# basePCB.net
KiCad netlist of a schematic drawn in EAGLE
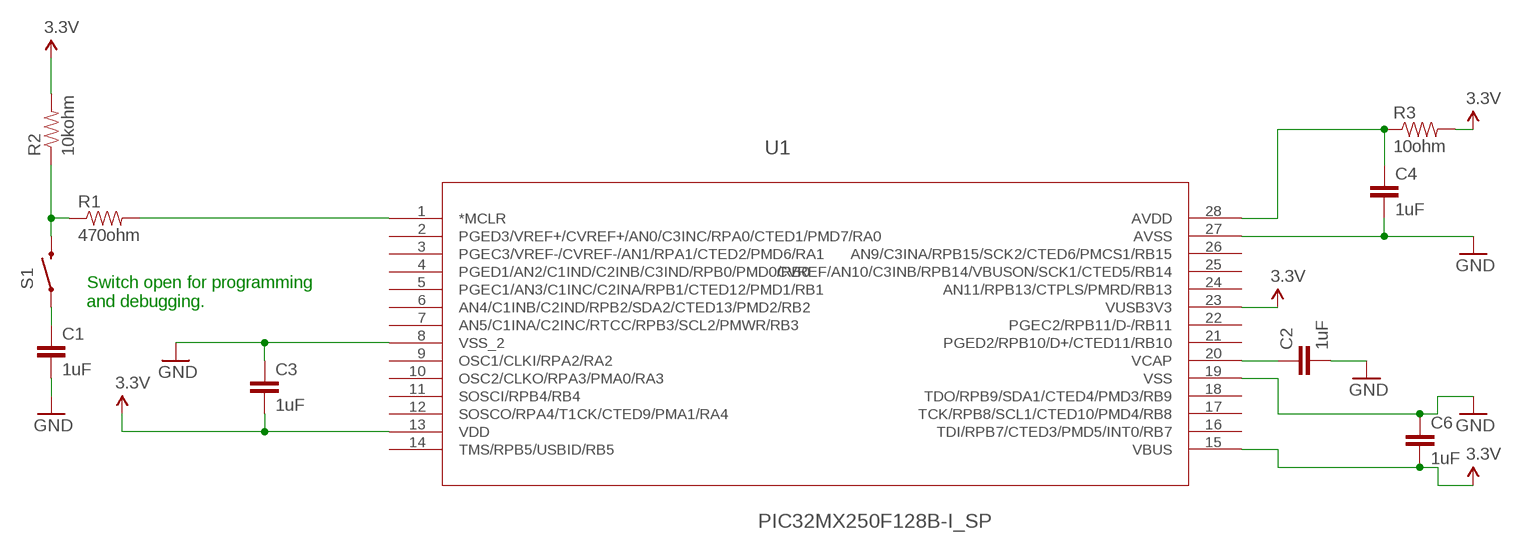
[diagram p0: schematic, sheet 1]

(export (version "E")
  (design (tool "Eeschema 10.0.6"))
  (components
    (comp (ref "C1")
      (value "1uF")
      (footprint "eagle-import:CAP-PTH-SMALL")
      (libsource (lib "eagle-import") (part "CAPPTH"))
    )
    (comp (ref "C2")
      (value "1uF")
      (footprint "eagle-import:CAP-PTH-SMALL")
      (libsource (lib "eagle-import") (part "CAPPTH"))
    )
    (comp (ref "C3")
      (value "1uF")
      (footprint "eagle-import:CAP-PTH-SMALL")
      (libsource (lib "eagle-import") (part "CAPPTH"))
    )
    (comp (ref "C4")
      (value "1uF")
      (footprint "eagle-import:CAP-PTH-SMALL")
      (libsource (lib "eagle-import") (part "CAPPTH"))
    )
    (comp (ref "C6")
      (value "1uF")
      (footprint "eagle-import:CAP-PTH-SMALL")
      (libsource (lib "eagle-import") (part "CAPPTH"))
    )
    (comp (ref "R1")
      (value "470ohm")
      (footprint "eagle-import:AXIAL-0.4")
      (libsource (lib "eagle-import") (part "RESISTORPTH-1/4W"))
    )
    (comp (ref "R2")
      (value "10kohm")
      (footprint "eagle-import:AXIAL-0.4")
      (libsource (lib "eagle-import") (part "RESISTORPTH-1/4W"))
    )
    (comp (ref "R3")
      (value "10ohm")
      (footprint "eagle-import:AXIAL-0.4")
      (libsource (lib "eagle-import") (part "RESISTORPTH-1/4W"))
    )
    (comp (ref "S1")
      (value "SWITCH-MOMENTARY-2SMD-1101NE")
      (footprint "eagle-import:TACTILE-SWITCH-1101NE")
      (libsource (lib "eagle-import") (part "SWITCH-MOMENTARY-2SMD-1101NE"))
    )
    (comp (ref "U1")
      (value "PIC32MX250F128B-I_SP")
      (footprint "eagle-import:SPDIP28_300MC")
      (libsource (lib "eagle-import") (part "PIC32MX250F128B-I_SP"))
    )
  )
  (nets
    (net (code "1") (name "3.3V") (class "Default")
      (node (ref "C3") (pin "2") (pinfunction "2_2") (pintype "passive"))
      (node (ref "C6") (pin "2") (pinfunction "2_2") (pintype "passive"))
      (node (ref "R2") (pin "P$2") (pinfunction "2_P$2") (pintype "passive"))
      (node (ref "R3") (pin "P$2") (pinfunction "2_P$2") (pintype "passive"))
      (node (ref "U1") (pin "13") (pinfunction "VDD_13") (pintype "power_in"))
      (node (ref "U1") (pin "15") (pinfunction "VBUS_15") (pintype "power_in"))
      (node (ref "U1") (pin "23") (pinfunction "VUSB3V3_23") (pintype "power_in"))
    )
    (net (code "2") (name "GND") (class "Default")
      (node (ref "C1") (pin "2") (pinfunction "2_2") (pintype "passive"))
      (node (ref "C2") (pin "2") (pinfunction "2_2") (pintype "passive"))
      (node (ref "C3") (pin "1") (pinfunction "1_1") (pintype "passive"))
      (node (ref "C4") (pin "2") (pinfunction "2_2") (pintype "passive"))
      (node (ref "C6") (pin "1") (pinfunction "1_1") (pintype "passive"))
      (node (ref "U1") (pin "19") (pinfunction "VSS_19") (pintype "power_in"))
      (node (ref "U1") (pin "27") (pinfunction "AVSS_27") (pintype "power_in"))
      (node (ref "U1") (pin "8") (pinfunction "VSS_2_8") (pintype "power_in"))
    )
    (net (code "3") (name "Net-(C1-Pad1)") (class "Default")
      (node (ref "C1") (pin "1") (pinfunction "1_1") (pintype "passive"))
      (node (ref "S1") (pin "1") (pinfunction "1_1") (pintype "passive"))
    )
    (net (code "4") (name "Net-(R1-1)") (class "Default")
      (node (ref "R1") (pin "P$1") (pinfunction "1_P$1") (pintype "passive"))
      (node (ref "R2") (pin "P$1") (pinfunction "1_P$1") (pintype "passive"))
      (node (ref "S1") (pin "2") (pinfunction "2_2") (pintype "passive"))
    )
    (net (code "5") (name "Net-(R1-2)") (class "Default")
      (node (ref "R1") (pin "P$2") (pinfunction "2_P$2") (pintype "passive"))
      (node (ref "U1") (pin "1") (pinfunction "*MCLR_1") (pintype "input"))
    )
    (net (code "6") (name "Net-(R3-1)") (class "Default")
      (node (ref "C4") (pin "1") (pinfunction "1_1") (pintype "passive"))
      (node (ref "R3") (pin "P$1") (pinfunction "1_P$1") (pintype "passive"))
      (node (ref "U1") (pin "28") (pinfunction "AVDD_28") (pintype "power_in"))
    )
    (net (code "7") (name "Net-(U1-VCAP)") (class "Default")
      (node (ref "C2") (pin "1") (pinfunction "1_1") (pintype "passive"))
      (node (ref "U1") (pin "20") (pinfunction "VCAP_20") (pintype "power_in"))
    )
    (net (code "8") (name "unconnected-(U1-AN4{slash}C1INB{slash}C2IND{slash}RPB2{slash}SDA2{slash}CTED13{slash}PMD2{slash}RB2-Pad6)") (class "Default")
      (node (ref "U1") (pin "6") (pinfunction "AN4/C1INB/C2IND/RPB2/SDA2/CTED13/PMD2/RB2_6") (pintype "bidirectional"))
    )
    (net (code "9") (name "unconnected-(U1-AN5{slash}C1INA{slash}C2INC{slash}RTCC{slash}RPB3{slash}SCL2{slash}PMWR{slash}RB3-Pad7)") (class "Default")
      (node (ref "U1") (pin "7") (pinfunction "AN5/C1INA/C2INC/RTCC/RPB3/SCL2/PMWR/RB3_7") (pintype "bidirectional"))
    )
    (net (code "10") (name "unconnected-(U1-AN9{slash}C3INA{slash}RPB15{slash}SCK2{slash}CTED6{slash}PMCS1{slash}RB15-Pad26)") (class "Default")
      (node (ref "U1") (pin "26") (pinfunction "AN9/C3INA/RPB15/SCK2/CTED6/PMCS1/RB15_26") (pintype "bidirectional"))
    )
    (net (code "11") (name "unconnected-(U1-AN11{slash}RPB13{slash}CTPLS{slash}PMRD{slash}RB13-Pad24)") (class "Default")
      (node (ref "U1") (pin "24") (pinfunction "AN11/RPB13/CTPLS/PMRD/RB13_24") (pintype "bidirectional"))
    )
    (net (code "12") (name "unconnected-(U1-CVREF{slash}AN10{slash}C3INB{slash}RPB14{slash}VBUSON{slash}SCK1{slash}CTED5{slash}RB14-Pad25)") (class "Default")
      (node (ref "U1") (pin "25") (pinfunction "CVREF/AN10/C3INB/RPB14/VBUSON/SCK1/CTED5/RB14_25") (pintype "bidirectional"))
    )
    (net (code "13") (name "unconnected-(U1-OSC1{slash}CLKI{slash}RPA2{slash}RA2-Pad9)") (class "Default")
      (node (ref "U1") (pin "9") (pinfunction "OSC1/CLKI/RPA2/RA2_9") (pintype "bidirectional"))
    )
    (net (code "14") (name "unconnected-(U1-OSC2{slash}CLKO{slash}RPA3{slash}PMA0{slash}RA3-Pad10)") (class "Default")
      (node (ref "U1") (pin "10") (pinfunction "OSC2/CLKO/RPA3/PMA0/RA3_10") (pintype "bidirectional"))
    )
    (net (code "15") (name "unconnected-(U1-PGEC1{slash}AN3{slash}C1INC{slash}C2INA{slash}RPB1{slash}CTED12{slash}PMD1{slash}RB1-Pad5)") (class "Default")
      (node (ref "U1") (pin "5") (pinfunction "PGEC1/AN3/C1INC/C2INA/RPB1/CTED12/PMD1/RB1_5") (pintype "bidirectional"))
    )
    (net (code "16") (name "unconnected-(U1-PGEC2{slash}RPB11{slash}D-{slash}RB11-Pad22)") (class "Default")
      (node (ref "U1") (pin "22") (pinfunction "PGEC2/RPB11/D-/RB11_22") (pintype "bidirectional"))
    )
    (net (code "17") (name "unconnected-(U1-PGEC3{slash}VREF-{slash}CVREF-{slash}AN1{slash}RPA1{slash}CTED2{slash}PMD6{slash}RA1-Pad3)") (class "Default")
      (node (ref "U1") (pin "3") (pinfunction "PGEC3/VREF-/CVREF-/AN1/RPA1/CTED2/PMD6/RA1_3") (pintype "bidirectional"))
    )
    (net (code "18") (name "unconnected-(U1-PGED1{slash}AN2{slash}C1IND{slash}C2INB{slash}C3IND{slash}RPB0{slash}PMD0{slash}RB0-Pad4)") (class "Default")
      (node (ref "U1") (pin "4") (pinfunction "PGED1/AN2/C1IND/C2INB/C3IND/RPB0/PMD0/RB0_4") (pintype "bidirectional"))
    )
    (net (code "19") (name "unconnected-(U1-PGED2{slash}RPB10{slash}D+{slash}CTED11{slash}RB10-Pad21)") (class "Default")
      (node (ref "U1") (pin "21") (pinfunction "PGED2/RPB10/D+/CTED11/RB10_21") (pintype "bidirectional"))
    )
    (net (code "20") (name "unconnected-(U1-PGED3{slash}VREF+{slash}CVREF+{slash}AN0{slash}C3INC{slash}RPA0{slash}CTED1{slash}PMD7{slash}RA0-Pad2)") (class "Default")
      (node (ref "U1") (pin "2") (pinfunction "PGED3/VREF+/CVREF+/AN0/C3INC/RPA0/CTED1/PMD7/RA0_2") (pintype "bidirectional"))
    )
    (net (code "21") (name "unconnected-(U1-SOSCI{slash}RPB4{slash}RB4-Pad11)") (class "Default")
      (node (ref "U1") (pin "11") (pinfunction "SOSCI/RPB4/RB4_11") (pintype "bidirectional"))
    )
    (net (code "22") (name "unconnected-(U1-SOSCO{slash}RPA4{slash}T1CK{slash}CTED9{slash}PMA1{slash}RA4-Pad12)") (class "Default")
      (node (ref "U1") (pin "12") (pinfunction "SOSCO/RPA4/T1CK/CTED9/PMA1/RA4_12") (pintype "bidirectional"))
    )
    (net (code "23") (name "unconnected-(U1-TCK{slash}RPB8{slash}SCL1{slash}CTED10{slash}PMD4{slash}RB8-Pad17)") (class "Default")
      (node (ref "U1") (pin "17") (pinfunction "TCK/RPB8/SCL1/CTED10/PMD4/RB8_17") (pintype "bidirectional"))
    )
    (net (code "24") (name "unconnected-(U1-TDI{slash}RPB7{slash}CTED3{slash}PMD5{slash}INT0{slash}RB7-Pad16)") (class "Default")
      (node (ref "U1") (pin "16") (pinfunction "TDI/RPB7/CTED3/PMD5/INT0/RB7_16") (pintype "bidirectional"))
    )
    (net (code "25") (name "unconnected-(U1-TDO{slash}RPB9{slash}SDA1{slash}CTED4{slash}PMD3{slash}RB9-Pad18)") (class "Default")
      (node (ref "U1") (pin "18") (pinfunction "TDO/RPB9/SDA1/CTED4/PMD3/RB9_18") (pintype "bidirectional"))
    )
    (net (code "26") (name "unconnected-(U1-TMS{slash}RPB5{slash}USBID{slash}RB5-Pad14)") (class "Default")
      (node (ref "U1") (pin "14") (pinfunction "TMS/RPB5/USBID/RB5_14") (pintype "bidirectional"))
    )
  )
)
